# BottleBuddy-V1_1.net
KiCad netlist of a schematic drawn in EAGLE
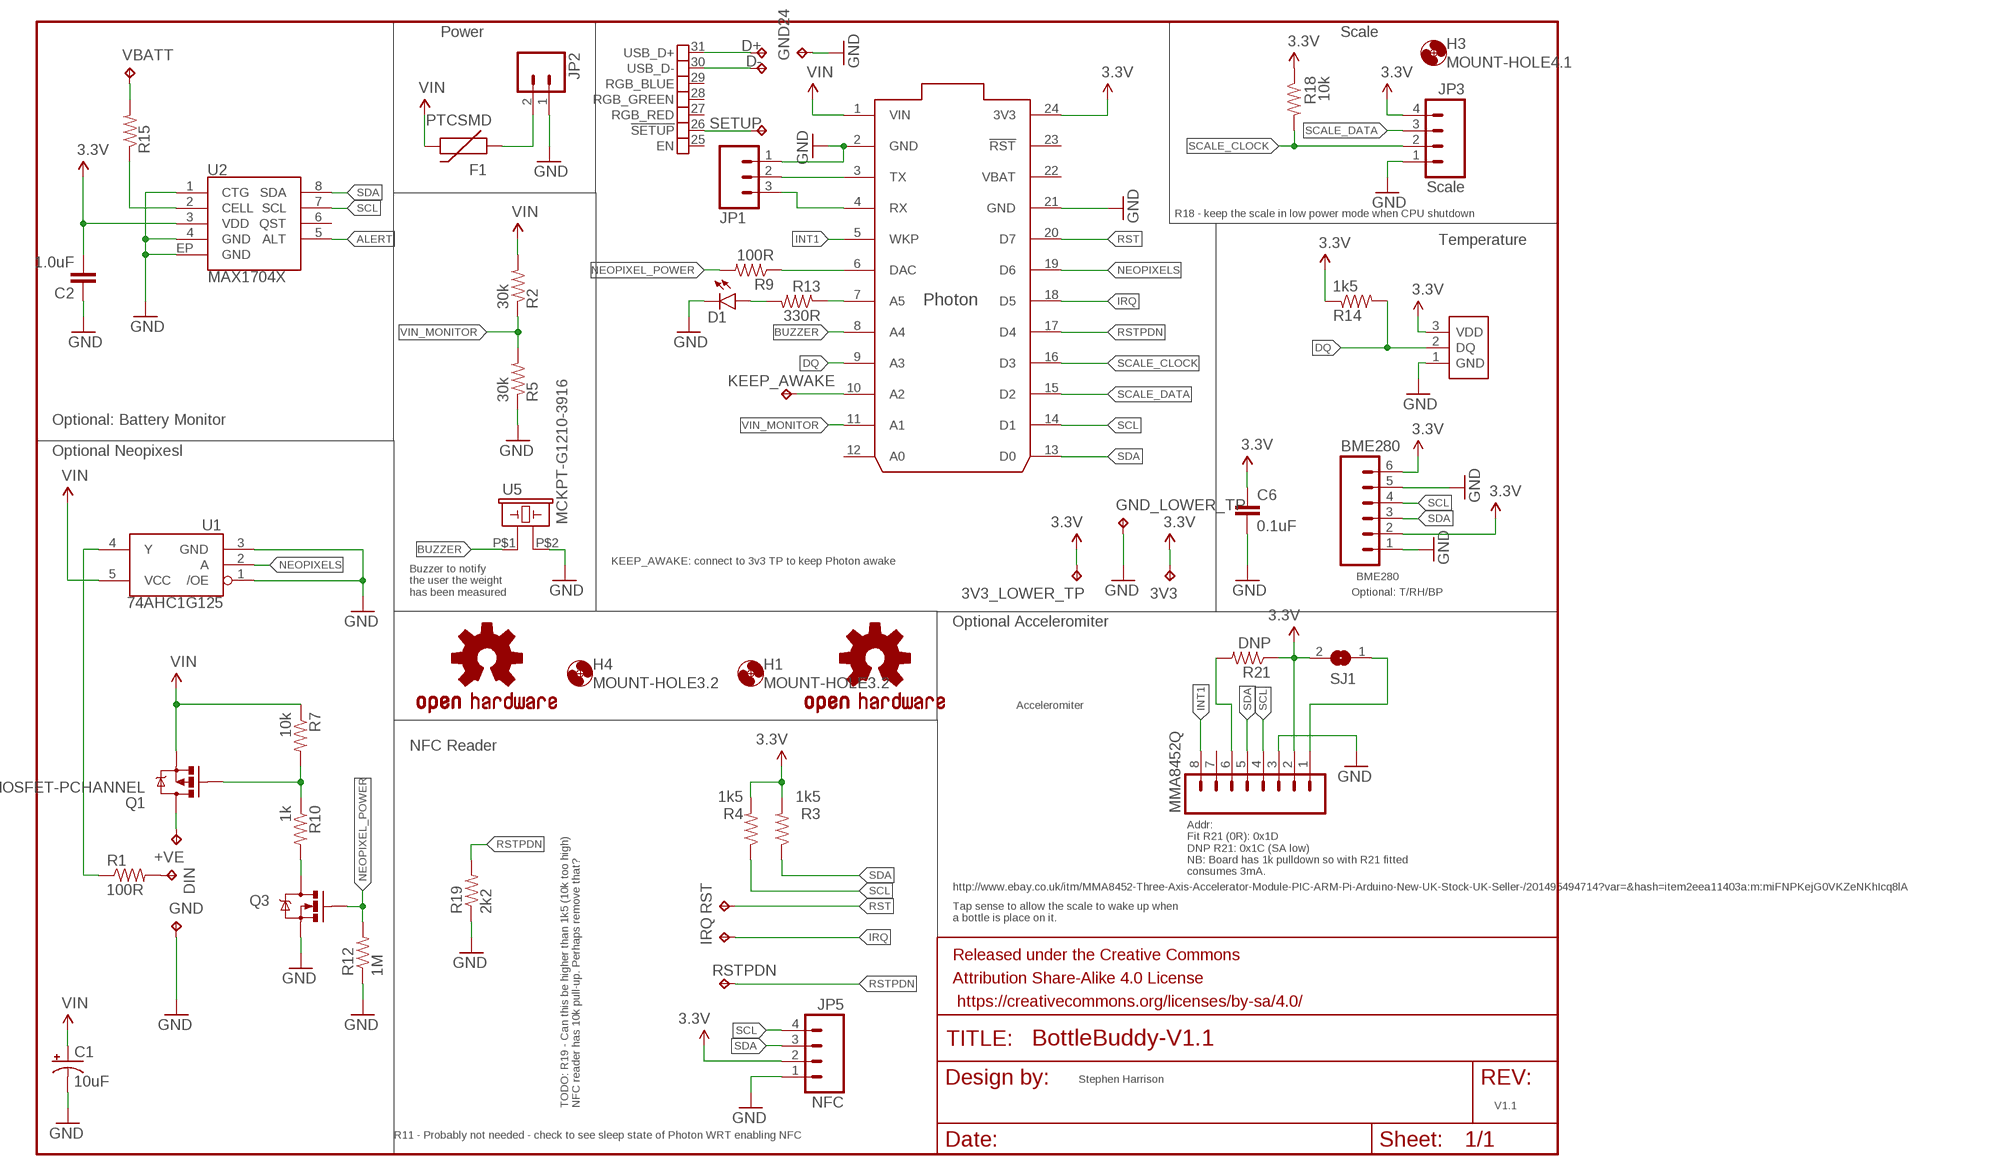
[diagram p0: schematic, sheet 1]

(export (version "E")
  (design (tool "Eeschema 10.0.6"))
  (components
    (comp (ref "+VE")
      (value "TPTP20R")
      (footprint "eagle-import:TP20R")
      (libsource (lib "eagle-import") (part "TPTP20R"))
    )
    (comp (ref "3V3")
      (value "TPTP20R")
      (footprint "eagle-import:TP20R")
      (libsource (lib "eagle-import") (part "TPTP20R"))
    )
    (comp (ref "3V3_LOWER_TP")
      (value "TPTP20R")
      (footprint "eagle-import:TP20R")
      (libsource (lib "eagle-import") (part "TPTP20R"))
    )
    (comp (ref "BME280")
      (value "M06SILK_FEMALE_PTH")
      (footprint "eagle-import:1X06")
      (libsource (lib "eagle-import") (part "M06SILK_FEMALE_PTH"))
    )
    (comp (ref "C1")
      (value "10uF")
      (footprint "eagle-import:EIA3216")
      (libsource (lib "eagle-import") (part "10UF-16V-10%(TANT)"))
    )
    (comp (ref "C2")
      (value "1.0uF")
      (footprint "eagle-import:0805-CAP")
      (libsource (lib "eagle-import") (part "1.0UF-25V-+80/-20(0805){dblquote}"))
    )
    (comp (ref "C6")
      (value "0.1uF")
      (footprint "eagle-import:0805")
      (libsource (lib "eagle-import") (part "CAP0805"))
    )
    (comp (ref "D+")
      (value "TPTP20R")
      (footprint "eagle-import:TP20R")
      (libsource (lib "eagle-import") (part "TPTP20R"))
    )
    (comp (ref "D-")
      (value "TPTP20R")
      (footprint "eagle-import:TP20R")
      (libsource (lib "eagle-import") (part "TPTP20R"))
    )
    (comp (ref "D1")
      (value "LED1206-BOTTOM")
      (footprint "eagle-import:LED-1206-BOTTOM")
      (libsource (lib "eagle-import") (part "LED1206-BOTTOM"))
    )
    (comp (ref "DIN")
      (value "TPTP20R")
      (footprint "eagle-import:TP20R")
      (libsource (lib "eagle-import") (part "TPTP20R"))
    )
    (comp (ref "F1")
      (value "PTCSMD")
      (footprint "eagle-import:PTC-1206")
      (libsource (lib "eagle-import") (part "PTCSMD"))
    )
    (comp (ref "FRAME1")
      (value "FRAME-LETTER")
      (footprint "eagle-import:CREATIVE_COMMONS")
      (libsource (lib "eagle-import") (part "FRAME-LETTER"))
    )
    (comp (ref "GND")
      (value "TPTP20R")
      (footprint "eagle-import:TP20R")
      (libsource (lib "eagle-import") (part "TPTP20R"))
    )
    (comp (ref "GND24")
      (value "TPTP20R")
      (footprint "eagle-import:TP20R")
      (libsource (lib "eagle-import") (part "TPTP20R"))
    )
    (comp (ref "GND_LOWER_TP")
      (value "TPTP20R")
      (footprint "eagle-import:TP20R")
      (libsource (lib "eagle-import") (part "TPTP20R"))
    )
    (comp (ref "H1")
      (value "MOUNT-HOLE3.2")
      (footprint "eagle-import:3,2")
      (libsource (lib "eagle-import") (part "MOUNT-HOLE3.2"))
    )
    (comp (ref "H3")
      (value "MOUNT-HOLE4.1")
      (footprint "eagle-import:4,1")
      (libsource (lib "eagle-import") (part "MOUNT-HOLE4.1"))
    )
    (comp (ref "H4")
      (value "MOUNT-HOLE3.2")
      (footprint "eagle-import:3,2")
      (libsource (lib "eagle-import") (part "MOUNT-HOLE3.2"))
    )
    (comp (ref "IRQ")
      (value "NFC IRQ")
      (footprint "eagle-import:TP20R")
      (libsource (lib "eagle-import") (part "TPTP20R"))
    )
    (comp (ref "JP1")
      (value "M03PTH")
      (footprint "eagle-import:1X03")
      (libsource (lib "eagle-import") (part "M03PTH"))
    )
    (comp (ref "JP2")
      (value "M02-JST-2MM-SMT")
      (footprint "eagle-import:JST-2-SMD")
      (libsource (lib "eagle-import") (part "M02-JST-2MM-SMT"))
    )
    (comp (ref "JP3")
      (value "Scale")
      (footprint "eagle-import:1X04")
      (libsource (lib "eagle-import") (part "M04PTH"))
    )
    (comp (ref "JP5")
      (value "NFC")
      (footprint "eagle-import:1X04")
      (libsource (lib "eagle-import") (part "M04PTH"))
    )
    (comp (ref "KEEP_AWAKE")
      (value "TPTP20R")
      (footprint "eagle-import:TP20R")
      (libsource (lib "eagle-import") (part "TPTP20R"))
    )
    (comp (ref "LOGO1")
      (value "OSHW-LOGOL")
      (footprint "eagle-import:OSHW-LOGO-L")
      (libsource (lib "eagle-import") (part "OSHW-LOGOL"))
    )
    (comp (ref "LOGO2")
      (value "OSHW-LOGOL")
      (footprint "eagle-import:OSHW-LOGO-L")
      (libsource (lib "eagle-import") (part "OSHW-LOGOL"))
    )
    (comp (ref "MMA8452Q")
      (value "M08SILK_FEMALE_PTH")
      (footprint "eagle-import:1X08")
      (libsource (lib "eagle-import") (part "M08SILK_FEMALE_PTH"))
    )
    (comp (ref "Q1")
      (value "MOSFET-PCHANNEL")
      (footprint "eagle-import:SOT23-3")
      (libsource (lib "eagle-import") (part "MOSFET-PCHANNEL"))
    )
    (comp (ref "Q3")
      (value "200mA/50V")
      (footprint "eagle-import:SOT23-3")
      (libsource (lib "eagle-import") (part "MOSFET-NCHANNELBSS138"))
    )
    (comp (ref "R1")
      (value "100R")
      (footprint "eagle-import:1206")
      (libsource (lib "eagle-import") (part "RESISTOR1206"))
    )
    (comp (ref "R2")
      (value "30k")
      (footprint "eagle-import:1206")
      (libsource (lib "eagle-import") (part "RESISTOR1206"))
    )
    (comp (ref "R3")
      (value "1k5")
      (footprint "eagle-import:1206")
      (libsource (lib "eagle-import") (part "RESISTOR1206"))
    )
    (comp (ref "R4")
      (value "1k5")
      (footprint "eagle-import:1206")
      (libsource (lib "eagle-import") (part "RESISTOR1206"))
    )
    (comp (ref "R5")
      (value "30k")
      (footprint "eagle-import:1206")
      (libsource (lib "eagle-import") (part "RESISTOR1206"))
    )
    (comp (ref "R7")
      (value "10k")
      (footprint "eagle-import:1206")
      (libsource (lib "eagle-import") (part "RESISTOR1206"))
    )
    (comp (ref "R9")
      (value "100R")
      (footprint "eagle-import:1206")
      (libsource (lib "eagle-import") (part "RESISTOR1206"))
    )
    (comp (ref "R10")
      (value "1k")
      (footprint "eagle-import:1206")
      (libsource (lib "eagle-import") (part "RESISTOR1206"))
    )
    (comp (ref "R12")
      (value "1M")
      (footprint "eagle-import:1206")
      (libsource (lib "eagle-import") (part "RESISTOR1206"))
    )
    (comp (ref "R13")
      (value "330R")
      (footprint "eagle-import:1206")
      (libsource (lib "eagle-import") (part "RESISTOR1206"))
    )
    (comp (ref "R14")
      (value "1k5")
      (footprint "eagle-import:1206")
      (libsource (lib "eagle-import") (part "RESISTOR1206"))
    )
    (comp (ref "R15")
      (value "RESISTOR1206")
      (footprint "eagle-import:1206")
      (libsource (lib "eagle-import") (part "RESISTOR1206"))
    )
    (comp (ref "R18")
      (value "10k")
      (footprint "eagle-import:1206")
      (libsource (lib "eagle-import") (part "RESISTOR1206"))
    )
    (comp (ref "R19")
      (value "2k2")
      (footprint "eagle-import:1206")
      (libsource (lib "eagle-import") (part "RESISTOR1206"))
    )
    (comp (ref "R21")
      (value "DNP")
      (footprint "eagle-import:1206")
      (libsource (lib "eagle-import") (part "RESISTOR1206"))
    )
    (comp (ref "RST")
      (value "TPTP20R")
      (footprint "eagle-import:TP20R")
      (libsource (lib "eagle-import") (part "TPTP20R"))
    )
    (comp (ref "RSTPDN")
      (value "NFC IRQ")
      (footprint "eagle-import:TP20R")
      (libsource (lib "eagle-import") (part "TPTP20R"))
    )
    (comp (ref "S1")
      (value "SENSOR-DS18B20")
      (footprint "eagle-import:TO-92-TRIANGLE")
      (libsource (lib "eagle-import") (part "SENSOR-DS18B20"))
    )
    (comp (ref "SETUP")
      (value "TPTP20R")
      (footprint "eagle-import:TP20R")
      (libsource (lib "eagle-import") (part "TPTP20R"))
    )
    (comp (ref "SJ1") (value "SJ") (footprint "eagle-import:SJ") (libsource (lib "eagle-import") (part "SJ")))
    (comp (ref "U$1")
      (value "PHOTON_SMD")
      (footprint "eagle-import:PHOTON_SMD")
      (libsource (lib "eagle-import") (part "PHOTON_SMD"))
    )
    (comp (ref "U1")
      (value "74AHC1G125")
      (footprint "eagle-import:SOT23-5")
      (libsource (lib "eagle-import") (part "74AHC1G125"))
    )
    (comp (ref "U2")
      (value "MAX1704X")
      (footprint "eagle-import:TDFN-8")
      (libsource (lib "eagle-import") (part "MAX1704X"))
    )
    (comp (ref "U5")
      (value "MCKPT-G1210-3916")
      (footprint "eagle-import:BUZZER-12MM")
      (libsource (lib "eagle-import") (part "MCKPT-G1210-3916"))
    )
    (comp (ref "VBATT")
      (value "TPTP20R")
      (footprint "eagle-import:TP20R")
      (libsource (lib "eagle-import") (part "TPTP20R"))
    )
  )
  (nets
    (net (code "1") (name "/VBAT") (class "Default")
      (node (ref "U$1") (pin "22") (pinfunction "VBAT_22") (pintype "power_in"))
    )
    (net (code "2") (name "3.3V") (class "Default")
      (node (ref "3V3") (pin "TP") (pinfunction "TP_TP") (pintype "input"))
      (node (ref "3V3_LOWER_TP") (pin "TP") (pinfunction "TP_TP") (pintype "input"))
      (node (ref "BME280") (pin "2") (pinfunction "2_2") (pintype "passive"))
      (node (ref "BME280") (pin "6") (pinfunction "6_6") (pintype "passive"))
      (node (ref "C2") (pin "2") (pinfunction "2_2") (pintype "passive"))
      (node (ref "C6") (pin "1") (pinfunction "1_1") (pintype "passive"))
      (node (ref "JP3") (pin "4") (pinfunction "4_4") (pintype "passive"))
      (node (ref "JP5") (pin "2") (pinfunction "2_2") (pintype "passive"))
      (node (ref "MMA8452Q") (pin "2") (pinfunction "2_2") (pintype "passive"))
      (node (ref "R14") (pin "1") (pinfunction "1_1") (pintype "passive"))
      (node (ref "R18") (pin "1") (pinfunction "1_1") (pintype "passive"))
      (node (ref "R21") (pin "1") (pinfunction "1_1") (pintype "passive"))
      (node (ref "R3") (pin "2") (pinfunction "2_2") (pintype "passive"))
      (node (ref "R4") (pin "2") (pinfunction "2_2") (pintype "passive"))
      (node (ref "S1") (pin "3") (pinfunction "VDD_3") (pintype "bidirectional"))
      (node (ref "SJ1") (pin "2") (pinfunction "2_2") (pintype "passive"))
      (node (ref "U$1") (pin "24") (pinfunction "3V3_24") (pintype "power_in"))
      (node (ref "U2") (pin "3") (pinfunction "VDD_3") (pintype "bidirectional"))
    )
    (net (code "3") (name "ALERT") (class "Default")
      (node (ref "U2") (pin "5") (pinfunction "ALT_5") (pintype "bidirectional"))
    )
    (net (code "4") (name "BUZZER") (class "Default")
      (node (ref "U$1") (pin "8") (pinfunction "A4_8") (pintype "bidirectional"))
      (node (ref "U5") (pin "P$1") (pinfunction "1_P$1") (pintype "passive"))
    )
    (net (code "5") (name "DQ") (class "Default")
      (node (ref "R14") (pin "2") (pinfunction "2_2") (pintype "passive"))
      (node (ref "S1") (pin "2") (pinfunction "DQ_2") (pintype "bidirectional"))
      (node (ref "U$1") (pin "9") (pinfunction "A3_9") (pintype "bidirectional"))
    )
    (net (code "6") (name "GND") (class "Default")
      (node (ref "BME280") (pin "1") (pinfunction "1_1") (pintype "passive"))
      (node (ref "BME280") (pin "5") (pinfunction "5_5") (pintype "passive"))
      (node (ref "C1") (pin "C") (pinfunction "-_C") (pintype "passive"))
      (node (ref "C2") (pin "1") (pinfunction "1_1") (pintype "passive"))
      (node (ref "C6") (pin "2") (pinfunction "2_2") (pintype "passive"))
      (node (ref "D1") (pin "C") (pinfunction "C_C") (pintype "passive"))
      (node (ref "GND") (pin "TP") (pinfunction "TP_TP") (pintype "input"))
      (node (ref "GND24") (pin "TP") (pinfunction "TP_TP") (pintype "input"))
      (node (ref "GND_LOWER_TP") (pin "TP") (pinfunction "TP_TP") (pintype "input"))
      (node (ref "JP1") (pin "1") (pinfunction "1_1") (pintype "passive"))
      (node (ref "JP2") (pin "1") (pinfunction "2_1") (pintype "passive"))
      (node (ref "JP3") (pin "1") (pinfunction "1_1") (pintype "passive"))
      (node (ref "JP5") (pin "1") (pinfunction "1_1") (pintype "passive"))
      (node (ref "MMA8452Q") (pin "3") (pinfunction "3_3") (pintype "passive"))
      (node (ref "Q3") (pin "2") (pinfunction "S_2") (pintype "passive"))
      (node (ref "R12") (pin "1") (pinfunction "1_1") (pintype "passive"))
      (node (ref "R19") (pin "1") (pinfunction "1_1") (pintype "passive"))
      (node (ref "R5") (pin "1") (pinfunction "1_1") (pintype "passive"))
      (node (ref "S1") (pin "1") (pinfunction "GND_1") (pintype "bidirectional"))
      (node (ref "U$1") (pin "2") (pinfunction "GND_2") (pintype "power_in"))
      (node (ref "U$1") (pin "21") (pinfunction "GND_21") (pintype "power_in"))
      (node (ref "U1") (pin "1") (pinfunction "/OE_1") (pintype "bidirectional"))
      (node (ref "U1") (pin "3") (pinfunction "GND_3") (pintype "bidirectional"))
      (node (ref "U2") (pin "1") (pinfunction "CTG_1") (pintype "bidirectional"))
      (node (ref "U2") (pin "4") (pinfunction "GND_4") (pintype "bidirectional"))
      (node (ref "U2") (pin "EP") (pinfunction "GND_EP") (pintype "bidirectional"))
      (node (ref "U5") (pin "P$2") (pinfunction "2_P$2") (pintype "passive"))
    )
    (net (code "7") (name "INT1") (class "Default")
      (node (ref "MMA8452Q") (pin "8") (pinfunction "8_8") (pintype "passive"))
      (node (ref "U$1") (pin "5") (pinfunction "WKP_5") (pintype "bidirectional"))
    )
    (net (code "8") (name "IRQ") (class "Default")
      (node (ref "IRQ") (pin "TP") (pinfunction "TP_TP") (pintype "input"))
      (node (ref "U$1") (pin "18") (pinfunction "D5_18") (pintype "bidirectional"))
    )
    (net (code "9") (name "NEOPIXELS") (class "Default")
      (node (ref "U$1") (pin "19") (pinfunction "D6_19") (pintype "bidirectional"))
      (node (ref "U1") (pin "2") (pinfunction "A_2") (pintype "bidirectional"))
    )
    (net (code "10") (name "NEOPIXEL_POWER") (class "Default")
      (node (ref "Q3") (pin "1") (pinfunction "G_1") (pintype "passive"))
      (node (ref "R12") (pin "2") (pinfunction "2_2") (pintype "passive"))
      (node (ref "R9") (pin "2") (pinfunction "2_2") (pintype "passive"))
    )
    (net (code "11") (name "Net-(D1-PadA)") (class "Default")
      (node (ref "D1") (pin "A") (pinfunction "A_A") (pintype "passive"))
      (node (ref "R13") (pin "2") (pinfunction "2_2") (pintype "passive"))
    )
    (net (code "12") (name "Net-(DIN-PadTP)") (class "Default")
      (node (ref "DIN") (pin "TP") (pinfunction "TP_TP") (pintype "input"))
      (node (ref "R1") (pin "2") (pinfunction "2_2") (pintype "passive"))
    )
    (net (code "13") (name "Net-(JP2-1)") (class "Default")
      (node (ref "F1") (pin "1") (pinfunction "1_1") (pintype "bidirectional"))
      (node (ref "JP2") (pin "2") (pinfunction "1_2") (pintype "passive"))
    )
    (net (code "14") (name "Net-(MMA8452Q-Pad1)") (class "Default")
      (node (ref "MMA8452Q") (pin "1") (pinfunction "1_1") (pintype "passive"))
      (node (ref "SJ1") (pin "1") (pinfunction "1_1") (pintype "passive"))
    )
    (net (code "15") (name "Net-(MMA8452Q-Pad6)") (class "Default")
      (node (ref "MMA8452Q") (pin "6") (pinfunction "6_6") (pintype "passive"))
      (node (ref "R21") (pin "2") (pinfunction "2_2") (pintype "passive"))
    )
    (net (code "16") (name "Net-(Q1-D)") (class "Default")
      (node (ref "+VE") (pin "TP") (pinfunction "TP_TP") (pintype "input"))
      (node (ref "Q1") (pin "3") (pinfunction "D_3") (pintype "passive"))
    )
    (net (code "17") (name "Net-(Q1-G)") (class "Default")
      (node (ref "Q1") (pin "1") (pinfunction "G_1") (pintype "passive"))
      (node (ref "R10") (pin "1") (pinfunction "1_1") (pintype "passive"))
      (node (ref "R7") (pin "2") (pinfunction "2_2") (pintype "passive"))
    )
    (net (code "18") (name "Net-(Q3-D)") (class "Default")
      (node (ref "Q3") (pin "3") (pinfunction "D_3") (pintype "passive"))
      (node (ref "R10") (pin "2") (pinfunction "2_2") (pintype "passive"))
    )
    (net (code "19") (name "Net-(R15-Pad2)") (class "Default")
      (node (ref "R15") (pin "2") (pinfunction "2_2") (pintype "passive"))
      (node (ref "VBATT") (pin "TP") (pinfunction "TP_TP") (pintype "input"))
    )
    (net (code "20") (name "Net-(U$1A-A2)") (class "Default")
      (node (ref "KEEP_AWAKE") (pin "TP") (pinfunction "TP_TP") (pintype "input"))
      (node (ref "U$1") (pin "10") (pinfunction "A2_10") (pintype "bidirectional"))
    )
    (net (code "21") (name "Net-(U$1A-A5)") (class "Default")
      (node (ref "R13") (pin "1") (pinfunction "1_1") (pintype "passive"))
      (node (ref "U$1") (pin "7") (pinfunction "A5_7") (pintype "bidirectional"))
    )
    (net (code "22") (name "Net-(U$1A-DAC)") (class "Default")
      (node (ref "R9") (pin "1") (pinfunction "1_1") (pintype "passive"))
      (node (ref "U$1") (pin "6") (pinfunction "DAC_6") (pintype "bidirectional"))
    )
    (net (code "23") (name "Net-(U$1A-RX)") (class "Default")
      (node (ref "JP1") (pin "3") (pinfunction "3_3") (pintype "passive"))
      (node (ref "U$1") (pin "4") (pinfunction "RX_4") (pintype "bidirectional"))
    )
    (net (code "24") (name "Net-(U$1A-TX)") (class "Default")
      (node (ref "JP1") (pin "2") (pinfunction "2_2") (pintype "passive"))
      (node (ref "U$1") (pin "3") (pinfunction "TX_3") (pintype "bidirectional"))
    )
    (net (code "25") (name "Net-(U$1B-USB_D+)") (class "Default")
      (node (ref "D+") (pin "TP") (pinfunction "TP_TP") (pintype "input"))
      (node (ref "U$1") (pin "31") (pinfunction "USB_D+_31") (pintype "bidirectional"))
    )
    (net (code "26") (name "Net-(U$1B-USB_D-)") (class "Default")
      (node (ref "D-") (pin "TP") (pinfunction "TP_TP") (pintype "input"))
      (node (ref "U$1") (pin "30") (pinfunction "USB_D-_30") (pintype "bidirectional"))
    )
    (net (code "27") (name "Net-(U$1B-~{SETUP})") (class "Default")
      (node (ref "SETUP") (pin "TP") (pinfunction "TP_TP") (pintype "input"))
      (node (ref "U$1") (pin "26") (pinfunction "~{SETUP}_26") (pintype "bidirectional"))
    )
    (net (code "28") (name "Net-(U1-Y)") (class "Default")
      (node (ref "R1") (pin "1") (pinfunction "1_1") (pintype "passive"))
      (node (ref "U1") (pin "4") (pinfunction "Y_4") (pintype "bidirectional"))
    )
    (net (code "29") (name "Net-(U2-CELL)") (class "Default")
      (node (ref "R15") (pin "1") (pinfunction "1_1") (pintype "passive"))
      (node (ref "U2") (pin "2") (pinfunction "CELL_2") (pintype "bidirectional"))
    )
    (net (code "30") (name "RST") (class "Default")
      (node (ref "RST") (pin "TP") (pinfunction "TP_TP") (pintype "input"))
      (node (ref "U$1") (pin "20") (pinfunction "D7_20") (pintype "bidirectional"))
    )
    (net (code "31") (name "RSTPDN") (class "Default")
      (node (ref "R19") (pin "2") (pinfunction "2_2") (pintype "passive"))
      (node (ref "RSTPDN") (pin "TP") (pinfunction "TP_TP") (pintype "input"))
      (node (ref "U$1") (pin "17") (pinfunction "D4_17") (pintype "bidirectional"))
    )
    (net (code "32") (name "SCALE_CLOCK") (class "Default")
      (node (ref "JP3") (pin "2") (pinfunction "2_2") (pintype "passive"))
      (node (ref "R18") (pin "2") (pinfunction "2_2") (pintype "passive"))
      (node (ref "U$1") (pin "16") (pinfunction "D3_16") (pintype "bidirectional"))
    )
    (net (code "33") (name "SCALE_DATA") (class "Default")
      (node (ref "JP3") (pin "3") (pinfunction "3_3") (pintype "passive"))
      (node (ref "U$1") (pin "15") (pinfunction "D2_15") (pintype "bidirectional"))
    )
    (net (code "34") (name "SCL") (class "Default")
      (node (ref "BME280") (pin "4") (pinfunction "4_4") (pintype "passive"))
      (node (ref "JP5") (pin "4") (pinfunction "4_4") (pintype "passive"))
      (node (ref "MMA8452Q") (pin "4") (pinfunction "4_4") (pintype "passive"))
      (node (ref "R4") (pin "1") (pinfunction "1_1") (pintype "passive"))
      (node (ref "U$1") (pin "14") (pinfunction "D1_14") (pintype "bidirectional"))
      (node (ref "U2") (pin "7") (pinfunction "SCL_7") (pintype "bidirectional"))
    )
    (net (code "35") (name "SDA") (class "Default")
      (node (ref "BME280") (pin "3") (pinfunction "3_3") (pintype "passive"))
      (node (ref "JP5") (pin "3") (pinfunction "3_3") (pintype "passive"))
      (node (ref "MMA8452Q") (pin "5") (pinfunction "5_5") (pintype "passive"))
      (node (ref "R3") (pin "1") (pinfunction "1_1") (pintype "passive"))
      (node (ref "U$1") (pin "13") (pinfunction "D0_13") (pintype "bidirectional"))
      (node (ref "U2") (pin "8") (pinfunction "SDA_8") (pintype "bidirectional"))
    )
    (net (code "36") (name "VIN") (class "Default")
      (node (ref "C1") (pin "A") (pinfunction "+_A") (pintype "passive"))
      (node (ref "F1") (pin "2") (pinfunction "2_2") (pintype "bidirectional"))
      (node (ref "Q1") (pin "2") (pinfunction "S_2") (pintype "passive"))
      (node (ref "R2") (pin "2") (pinfunction "2_2") (pintype "passive"))
      (node (ref "R7") (pin "1") (pinfunction "1_1") (pintype "passive"))
      (node (ref "U$1") (pin "1") (pinfunction "VIN_1") (pintype "power_in"))
      (node (ref "U1") (pin "5") (pinfunction "VCC_5") (pintype "bidirectional"))
    )
    (net (code "37") (name "VIN_MONITOR") (class "Default")
      (node (ref "R2") (pin "1") (pinfunction "1_1") (pintype "passive"))
      (node (ref "R5") (pin "2") (pinfunction "2_2") (pintype "passive"))
      (node (ref "U$1") (pin "11") (pinfunction "A1_11") (pintype "bidirectional"))
    )
    (net (code "38") (name "unconnected-(MMA8452Q-Pad7)") (class "Default")
      (node (ref "MMA8452Q") (pin "7") (pinfunction "7_7") (pintype "passive"))
    )
    (net (code "39") (name "unconnected-(U$1A-A0-Pad12)") (class "Default")
      (node (ref "U$1") (pin "12") (pinfunction "A0_12") (pintype "bidirectional"))
    )
    (net (code "40") (name "unconnected-(U$1A-~{RST}-Pad23)") (class "Default")
      (node (ref "U$1") (pin "23") (pinfunction "~{RST}_23") (pintype "bidirectional"))
    )
    (net (code "41") (name "unconnected-(U$1B-EN-Pad25)") (class "Default")
      (node (ref "U$1") (pin "25") (pinfunction "EN_25") (pintype "bidirectional"))
    )
    (net (code "42") (name "unconnected-(U$1B-RGB_BLUE-Pad29)") (class "Default")
      (node (ref "U$1") (pin "29") (pinfunction "RGB_BLUE_29") (pintype "bidirectional"))
    )
    (net (code "43") (name "unconnected-(U$1B-RGB_GREEN-Pad28)") (class "Default")
      (node (ref "U$1") (pin "28") (pinfunction "RGB_GREEN_28") (pintype "bidirectional"))
    )
    (net (code "44") (name "unconnected-(U$1B-RGB_RED-Pad27)") (class "Default")
      (node (ref "U$1") (pin "27") (pinfunction "RGB_RED_27") (pintype "bidirectional"))
    )
    (net (code "45") (name "unconnected-(U2-QST-Pad6)") (class "Default")
      (node (ref "U2") (pin "6") (pinfunction "QST_6") (pintype "bidirectional"))
    )
  )
)
